# minimumSystem.net
KiCad netlist of a schematic drawn in EAGLE
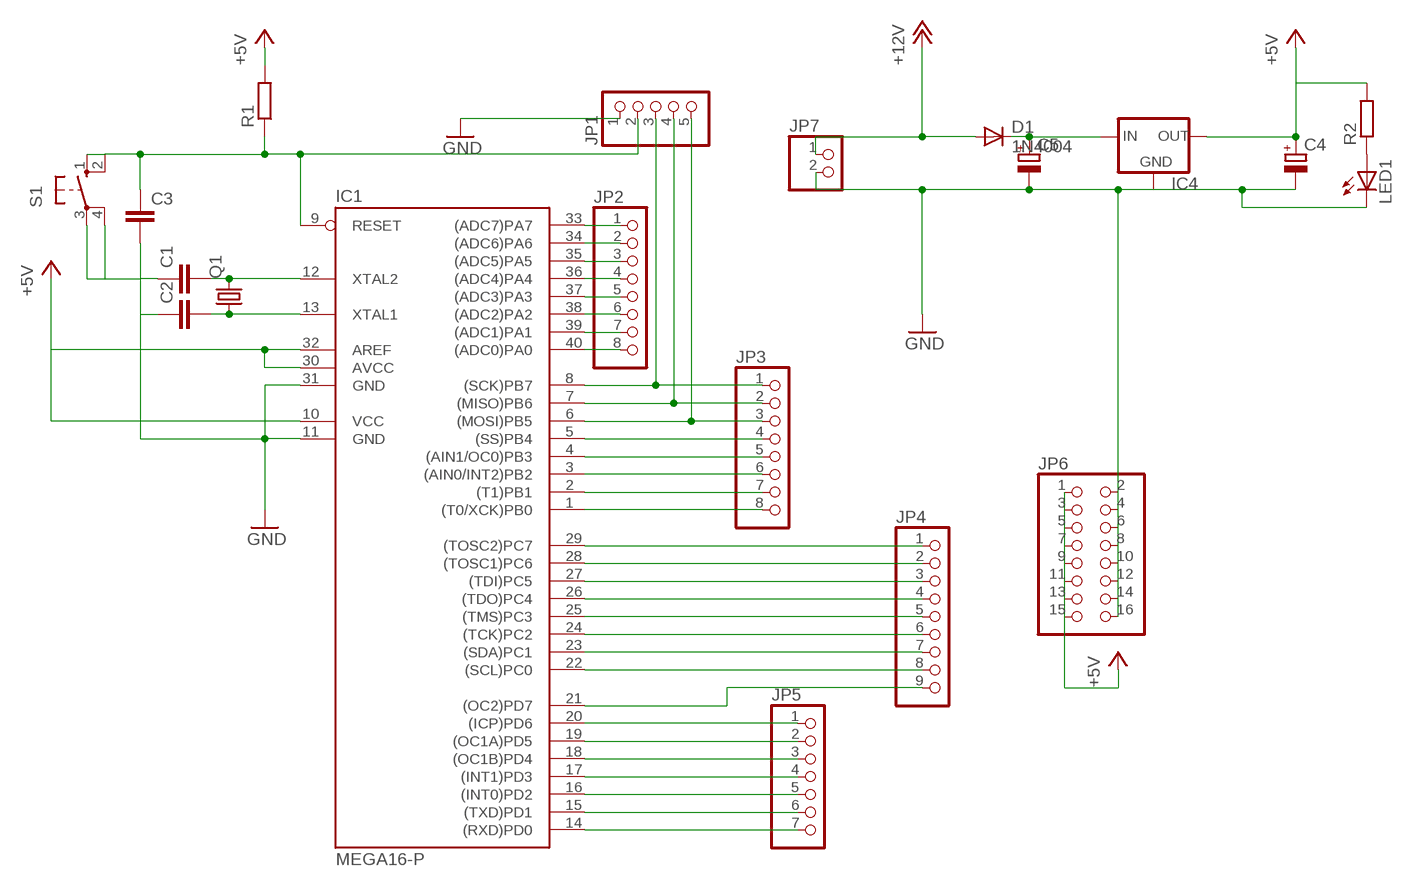
[diagram p0: schematic, sheet 1]

(export (version "E")
  (design (tool "Eeschema 10.0.6"))
  (components
    (comp (ref "C1")
      (value "C-EU025-024X044")
      (footprint "eagle-import:C025-024X044")
      (libsource (lib "eagle-import") (part "C-EU025-024X044"))
    )
    (comp (ref "C2")
      (value "C-EU025-024X044")
      (footprint "eagle-import:C025-024X044")
      (libsource (lib "eagle-import") (part "C-EU025-024X044"))
    )
    (comp (ref "C3")
      (value "C-EU050-025X075")
      (footprint "eagle-import:C050-025X075")
      (libsource (lib "eagle-import") (part "resistor_C-EU050-025X075"))
    )
    (comp (ref "C4")
      (value "CPOL-EUE2.5-5")
      (footprint "eagle-import:E2,5-5")
      (libsource (lib "eagle-import") (part "CPOL-EUE2.5-5"))
    )
    (comp (ref "C5")
      (value "CPOL-EUE2.5-5")
      (footprint "eagle-import:E2,5-5")
      (libsource (lib "eagle-import") (part "CPOL-EUE2.5-5"))
    )
    (comp (ref "D1")
      (value "1N4004")
      (footprint "eagle-import:DO41-10")
      (libsource (lib "eagle-import") (part "1N4004"))
    )
    (comp (ref "IC1")
      (value "MEGA16-P")
      (footprint "eagle-import:DIL40")
      (fields (field (name "MPN") "ATMEGA16-16PU"))
      (libsource (lib "eagle-import") (part "MEGA16-P"))
    )
    (comp (ref "IC4")
      (value "78XXS")
      (footprint "eagle-import:78XXS")
      (libsource (lib "eagle-import") (part "78XXS"))
    )
    (comp (ref "JP1")
      (value "PINHD-1X5")
      (footprint "eagle-import:1X05")
      (libsource (lib "eagle-import") (part "PINHD-1X5"))
    )
    (comp (ref "JP2")
      (value "PINHD-1X8")
      (footprint "eagle-import:1X08")
      (libsource (lib "eagle-import") (part "PINHD-1X8"))
    )
    (comp (ref "JP3")
      (value "PINHD-1X8")
      (footprint "eagle-import:1X08")
      (libsource (lib "eagle-import") (part "PINHD-1X8"))
    )
    (comp (ref "JP4")
      (value "PINHD-1X9")
      (footprint "eagle-import:1X09")
      (libsource (lib "eagle-import") (part "PINHD-1X9"))
    )
    (comp (ref "JP5")
      (value "PINHD-1X7")
      (footprint "eagle-import:1X07")
      (libsource (lib "eagle-import") (part "PINHD-1X7"))
    )
    (comp (ref "JP6")
      (value "PINHD-2X8")
      (footprint "eagle-import:2X08")
      (libsource (lib "eagle-import") (part "PINHD-2X8"))
    )
    (comp (ref "JP7")
      (value "PINHD-1X2")
      (footprint "eagle-import:1X02")
      (libsource (lib "eagle-import") (part "PINHD-1X2"))
    )
    (comp (ref "LED1")
      (value "LED5MM")
      (footprint "eagle-import:LED5MM")
      (libsource (lib "eagle-import") (part "LED5MM"))
    )
    (comp (ref "Q1")
      (value "CRYSTALHC49U-V")
      (footprint "eagle-import:HC49U-V")
      (libsource (lib "eagle-import") (part "CRYSTALHC49U-V"))
    )
    (comp (ref "R1")
      (value "R-EU_0204/7")
      (footprint "eagle-import:0204_7")
      (libsource (lib "eagle-import") (part "R-EU_0204/7"))
    )
    (comp (ref "R2")
      (value "R-EU_0204/7")
      (footprint "eagle-import:0204_7")
      (libsource (lib "eagle-import") (part "R-EU_0204/7"))
    )
    (comp (ref "S1")
      (value "10-XX")
      (footprint "eagle-import:B3F-10XX")
      (fields (field (name "MPN") "B3F-1000"))
      (libsource (lib "eagle-import") (part "10-XX"))
    )
  )
  (nets
    (net (code "1") (name "+5V") (class "Default")
      (node (ref "C4") (pin "+") (pinfunction "+_+") (pintype "passive"))
      (node (ref "IC1") (pin "10") (pinfunction "VCC_10") (pintype "power_in"))
      (node (ref "IC1") (pin "30") (pinfunction "AVCC_30") (pintype "power_in"))
      (node (ref "IC1") (pin "32") (pinfunction "AREF_32") (pintype "passive"))
      (node (ref "IC4") (pin "OUT") (pinfunction "OUT_OUT") (pintype "passive"))
      (node (ref "JP6") (pin "1") (pinfunction "1_1") (pintype "passive"))
      (node (ref "JP6") (pin "11") (pinfunction "11_11") (pintype "passive"))
      (node (ref "JP6") (pin "13") (pinfunction "13_13") (pintype "passive"))
      (node (ref "JP6") (pin "15") (pinfunction "15_15") (pintype "passive"))
      (node (ref "JP6") (pin "3") (pinfunction "3_3") (pintype "passive"))
      (node (ref "JP6") (pin "5") (pinfunction "5_5") (pintype "passive"))
      (node (ref "JP6") (pin "7") (pinfunction "7_7") (pintype "passive"))
      (node (ref "JP6") (pin "9") (pinfunction "9_9") (pintype "passive"))
      (node (ref "R1") (pin "2") (pinfunction "2_2") (pintype "passive"))
      (node (ref "R2") (pin "2") (pinfunction "2_2") (pintype "passive"))
    )
    (net (code "2") (name "+12V") (class "Default")
      (node (ref "D1") (pin "A") (pinfunction "A_A") (pintype "passive"))
      (node (ref "JP7") (pin "1") (pinfunction "1_1") (pintype "passive"))
    )
    (net (code "3") (name "GND") (class "Default")
      (node (ref "C1") (pin "1") (pinfunction "1_1") (pintype "passive"))
      (node (ref "C2") (pin "1") (pinfunction "1_1") (pintype "passive"))
      (node (ref "C3") (pin "2") (pinfunction "2_2") (pintype "passive"))
      (node (ref "C4") (pin "-") (pinfunction "-_-") (pintype "passive"))
      (node (ref "C5") (pin "-") (pinfunction "-_-") (pintype "passive"))
      (node (ref "IC1") (pin "11") (pinfunction "GND_11") (pintype "power_in"))
      (node (ref "IC1") (pin "31") (pinfunction "GND_31") (pintype "power_in"))
      (node (ref "IC4") (pin "GND") (pinfunction "GND_GND") (pintype "input"))
      (node (ref "JP1") (pin "1") (pinfunction "1_1") (pintype "passive"))
      (node (ref "JP6") (pin "10") (pinfunction "10_10") (pintype "passive"))
      (node (ref "JP6") (pin "12") (pinfunction "12_12") (pintype "passive"))
      (node (ref "JP6") (pin "14") (pinfunction "14_14") (pintype "passive"))
      (node (ref "JP6") (pin "16") (pinfunction "16_16") (pintype "passive"))
      (node (ref "JP6") (pin "2") (pinfunction "2_2") (pintype "passive"))
      (node (ref "JP6") (pin "4") (pinfunction "4_4") (pintype "passive"))
      (node (ref "JP6") (pin "6") (pinfunction "6_6") (pintype "passive"))
      (node (ref "JP6") (pin "8") (pinfunction "8_8") (pintype "passive"))
      (node (ref "JP7") (pin "2") (pinfunction "2_2") (pintype "passive"))
      (node (ref "LED1") (pin "K") (pinfunction "C_K") (pintype "passive"))
      (node (ref "S1") (pin "3") (pinfunction "P_3") (pintype "passive"))
      (node (ref "S1") (pin "4") (pinfunction "P1_4") (pintype "passive"))
    )
    (net (code "4") (name "Net-(C5-Pad+)") (class "Default")
      (node (ref "C5") (pin "+") (pinfunction "+_+") (pintype "passive"))
      (node (ref "D1") (pin "C") (pinfunction "C_C") (pintype "passive"))
      (node (ref "IC4") (pin "IN") (pinfunction "IN_IN") (pintype "input"))
    )
    (net (code "5") (name "Net-(IC1-(ADC0)PA0)") (class "Default")
      (node (ref "IC1") (pin "40") (pinfunction "(ADC0)PA0_40") (pintype "bidirectional"))
      (node (ref "JP2") (pin "8") (pinfunction "8_8") (pintype "passive"))
    )
    (net (code "6") (name "Net-(IC1-(ADC1)PA1)") (class "Default")
      (node (ref "IC1") (pin "39") (pinfunction "(ADC1)PA1_39") (pintype "bidirectional"))
      (node (ref "JP2") (pin "7") (pinfunction "7_7") (pintype "passive"))
    )
    (net (code "7") (name "Net-(IC1-(ADC2)PA2)") (class "Default")
      (node (ref "IC1") (pin "38") (pinfunction "(ADC2)PA2_38") (pintype "bidirectional"))
      (node (ref "JP2") (pin "6") (pinfunction "6_6") (pintype "passive"))
    )
    (net (code "8") (name "Net-(IC1-(ADC3)PA3)") (class "Default")
      (node (ref "IC1") (pin "37") (pinfunction "(ADC3)PA3_37") (pintype "bidirectional"))
      (node (ref "JP2") (pin "5") (pinfunction "5_5") (pintype "passive"))
    )
    (net (code "9") (name "Net-(IC1-(ADC4)PA4)") (class "Default")
      (node (ref "IC1") (pin "36") (pinfunction "(ADC4)PA4_36") (pintype "bidirectional"))
      (node (ref "JP2") (pin "4") (pinfunction "4_4") (pintype "passive"))
    )
    (net (code "10") (name "Net-(IC1-(ADC5)PA5)") (class "Default")
      (node (ref "IC1") (pin "35") (pinfunction "(ADC5)PA5_35") (pintype "bidirectional"))
      (node (ref "JP2") (pin "3") (pinfunction "3_3") (pintype "passive"))
    )
    (net (code "11") (name "Net-(IC1-(ADC6)PA6)") (class "Default")
      (node (ref "IC1") (pin "34") (pinfunction "(ADC6)PA6_34") (pintype "bidirectional"))
      (node (ref "JP2") (pin "2") (pinfunction "2_2") (pintype "passive"))
    )
    (net (code "12") (name "Net-(IC1-(ADC7)PA7)") (class "Default")
      (node (ref "IC1") (pin "33") (pinfunction "(ADC7)PA7_33") (pintype "bidirectional"))
      (node (ref "JP2") (pin "1") (pinfunction "1_1") (pintype "passive"))
    )
    (net (code "13") (name "Net-(IC1-(AIN0{slash}INT2)PB2)") (class "Default")
      (node (ref "IC1") (pin "3") (pinfunction "(AIN0/INT2)PB2_3") (pintype "bidirectional"))
      (node (ref "JP3") (pin "6") (pinfunction "6_6") (pintype "passive"))
    )
    (net (code "14") (name "Net-(IC1-(AIN1{slash}OC0)PB3)") (class "Default")
      (node (ref "IC1") (pin "4") (pinfunction "(AIN1/OC0)PB3_4") (pintype "bidirectional"))
      (node (ref "JP3") (pin "5") (pinfunction "5_5") (pintype "passive"))
    )
    (net (code "15") (name "Net-(IC1-(ICP)PD6)") (class "Default")
      (node (ref "IC1") (pin "20") (pinfunction "(ICP)PD6_20") (pintype "bidirectional"))
      (node (ref "JP5") (pin "1") (pinfunction "1_1") (pintype "passive"))
    )
    (net (code "16") (name "Net-(IC1-(INT0)PD2)") (class "Default")
      (node (ref "IC1") (pin "16") (pinfunction "(INT0)PD2_16") (pintype "bidirectional"))
      (node (ref "JP5") (pin "5") (pinfunction "5_5") (pintype "passive"))
    )
    (net (code "17") (name "Net-(IC1-(INT1)PD3)") (class "Default")
      (node (ref "IC1") (pin "17") (pinfunction "(INT1)PD3_17") (pintype "bidirectional"))
      (node (ref "JP5") (pin "4") (pinfunction "4_4") (pintype "passive"))
    )
    (net (code "18") (name "Net-(IC1-(MISO)PB6)") (class "Default")
      (node (ref "IC1") (pin "7") (pinfunction "(MISO)PB6_7") (pintype "bidirectional"))
      (node (ref "JP1") (pin "4") (pinfunction "4_4") (pintype "passive"))
      (node (ref "JP3") (pin "2") (pinfunction "2_2") (pintype "passive"))
    )
    (net (code "19") (name "Net-(IC1-(MOSI)PB5)") (class "Default")
      (node (ref "IC1") (pin "6") (pinfunction "(MOSI)PB5_6") (pintype "bidirectional"))
      (node (ref "JP1") (pin "5") (pinfunction "5_5") (pintype "passive"))
      (node (ref "JP3") (pin "3") (pinfunction "3_3") (pintype "passive"))
    )
    (net (code "20") (name "Net-(IC1-(OC1A)PD5)") (class "Default")
      (node (ref "IC1") (pin "19") (pinfunction "(OC1A)PD5_19") (pintype "bidirectional"))
      (node (ref "JP5") (pin "2") (pinfunction "2_2") (pintype "passive"))
    )
    (net (code "21") (name "Net-(IC1-(OC1B)PD4)") (class "Default")
      (node (ref "IC1") (pin "18") (pinfunction "(OC1B)PD4_18") (pintype "bidirectional"))
      (node (ref "JP5") (pin "3") (pinfunction "3_3") (pintype "passive"))
    )
    (net (code "22") (name "Net-(IC1-(OC2)PD7)") (class "Default")
      (node (ref "IC1") (pin "21") (pinfunction "(OC2)PD7_21") (pintype "bidirectional"))
      (node (ref "JP4") (pin "9") (pinfunction "9_9") (pintype "passive"))
    )
    (net (code "23") (name "Net-(IC1-(RXD)PD0)") (class "Default")
      (node (ref "IC1") (pin "14") (pinfunction "(RXD)PD0_14") (pintype "bidirectional"))
      (node (ref "JP5") (pin "7") (pinfunction "7_7") (pintype "passive"))
    )
    (net (code "24") (name "Net-(IC1-(SCK)PB7)") (class "Default")
      (node (ref "IC1") (pin "8") (pinfunction "(SCK)PB7_8") (pintype "bidirectional"))
      (node (ref "JP1") (pin "3") (pinfunction "3_3") (pintype "passive"))
      (node (ref "JP3") (pin "1") (pinfunction "1_1") (pintype "passive"))
    )
    (net (code "25") (name "Net-(IC1-(SCL)PC0)") (class "Default")
      (node (ref "IC1") (pin "22") (pinfunction "(SCL)PC0_22") (pintype "bidirectional"))
      (node (ref "JP4") (pin "8") (pinfunction "8_8") (pintype "passive"))
    )
    (net (code "26") (name "Net-(IC1-(SDA)PC1)") (class "Default")
      (node (ref "IC1") (pin "23") (pinfunction "(SDA)PC1_23") (pintype "bidirectional"))
      (node (ref "JP4") (pin "7") (pinfunction "7_7") (pintype "passive"))
    )
    (net (code "27") (name "Net-(IC1-(SS)PB4)") (class "Default")
      (node (ref "IC1") (pin "5") (pinfunction "(SS)PB4_5") (pintype "bidirectional"))
      (node (ref "JP3") (pin "4") (pinfunction "4_4") (pintype "passive"))
    )
    (net (code "28") (name "Net-(IC1-(T0{slash}XCK)PB0)") (class "Default")
      (node (ref "IC1") (pin "1") (pinfunction "(T0/XCK)PB0_1") (pintype "bidirectional"))
      (node (ref "JP3") (pin "8") (pinfunction "8_8") (pintype "passive"))
    )
    (net (code "29") (name "Net-(IC1-(T1)PB1)") (class "Default")
      (node (ref "IC1") (pin "2") (pinfunction "(T1)PB1_2") (pintype "bidirectional"))
      (node (ref "JP3") (pin "7") (pinfunction "7_7") (pintype "passive"))
    )
    (net (code "30") (name "Net-(IC1-(TCK)PC2)") (class "Default")
      (node (ref "IC1") (pin "24") (pinfunction "(TCK)PC2_24") (pintype "bidirectional"))
      (node (ref "JP4") (pin "6") (pinfunction "6_6") (pintype "passive"))
    )
    (net (code "31") (name "Net-(IC1-(TDI)PC5)") (class "Default")
      (node (ref "IC1") (pin "27") (pinfunction "(TDI)PC5_27") (pintype "bidirectional"))
      (node (ref "JP4") (pin "3") (pinfunction "3_3") (pintype "passive"))
    )
    (net (code "32") (name "Net-(IC1-(TDO)PC4)") (class "Default")
      (node (ref "IC1") (pin "26") (pinfunction "(TDO)PC4_26") (pintype "bidirectional"))
      (node (ref "JP4") (pin "4") (pinfunction "4_4") (pintype "passive"))
    )
    (net (code "33") (name "Net-(IC1-(TMS)PC3)") (class "Default")
      (node (ref "IC1") (pin "25") (pinfunction "(TMS)PC3_25") (pintype "bidirectional"))
      (node (ref "JP4") (pin "5") (pinfunction "5_5") (pintype "passive"))
    )
    (net (code "34") (name "Net-(IC1-(TOSC1)PC6)") (class "Default")
      (node (ref "IC1") (pin "28") (pinfunction "(TOSC1)PC6_28") (pintype "bidirectional"))
      (node (ref "JP4") (pin "2") (pinfunction "2_2") (pintype "passive"))
    )
    (net (code "35") (name "Net-(IC1-(TOSC2)PC7)") (class "Default")
      (node (ref "IC1") (pin "29") (pinfunction "(TOSC2)PC7_29") (pintype "bidirectional"))
      (node (ref "JP4") (pin "1") (pinfunction "1_1") (pintype "passive"))
    )
    (net (code "36") (name "Net-(IC1-(TXD)PD1)") (class "Default")
      (node (ref "IC1") (pin "15") (pinfunction "(TXD)PD1_15") (pintype "bidirectional"))
      (node (ref "JP5") (pin "6") (pinfunction "6_6") (pintype "passive"))
    )
    (net (code "37") (name "Net-(IC1-RESET)") (class "Default")
      (node (ref "C3") (pin "1") (pinfunction "1_1") (pintype "passive"))
      (node (ref "IC1") (pin "9") (pinfunction "RESET_9") (pintype "input"))
      (node (ref "JP1") (pin "2") (pinfunction "2_2") (pintype "passive"))
      (node (ref "R1") (pin "1") (pinfunction "1_1") (pintype "passive"))
      (node (ref "S1") (pin "1") (pinfunction "S_1") (pintype "passive"))
      (node (ref "S1") (pin "2") (pinfunction "S1_2") (pintype "passive"))
    )
    (net (code "38") (name "Net-(IC1-XTAL1)") (class "Default")
      (node (ref "C2") (pin "2") (pinfunction "2_2") (pintype "passive"))
      (node (ref "IC1") (pin "13") (pinfunction "XTAL1_13") (pintype "bidirectional"))
      (node (ref "Q1") (pin "1") (pinfunction "1_1") (pintype "passive"))
    )
    (net (code "39") (name "Net-(IC1-XTAL2)") (class "Default")
      (node (ref "C1") (pin "2") (pinfunction "2_2") (pintype "passive"))
      (node (ref "IC1") (pin "12") (pinfunction "XTAL2_12") (pintype "bidirectional"))
      (node (ref "Q1") (pin "2") (pinfunction "2_2") (pintype "passive"))
    )
    (net (code "40") (name "Net-(LED1-PadA)") (class "Default")
      (node (ref "LED1") (pin "A") (pinfunction "A_A") (pintype "passive"))
      (node (ref "R2") (pin "1") (pinfunction "1_1") (pintype "passive"))
    )
  )
)
